# 555_project_analog_swu_board_revA.net
KiCad netlist of a schematic drawn in EAGLE
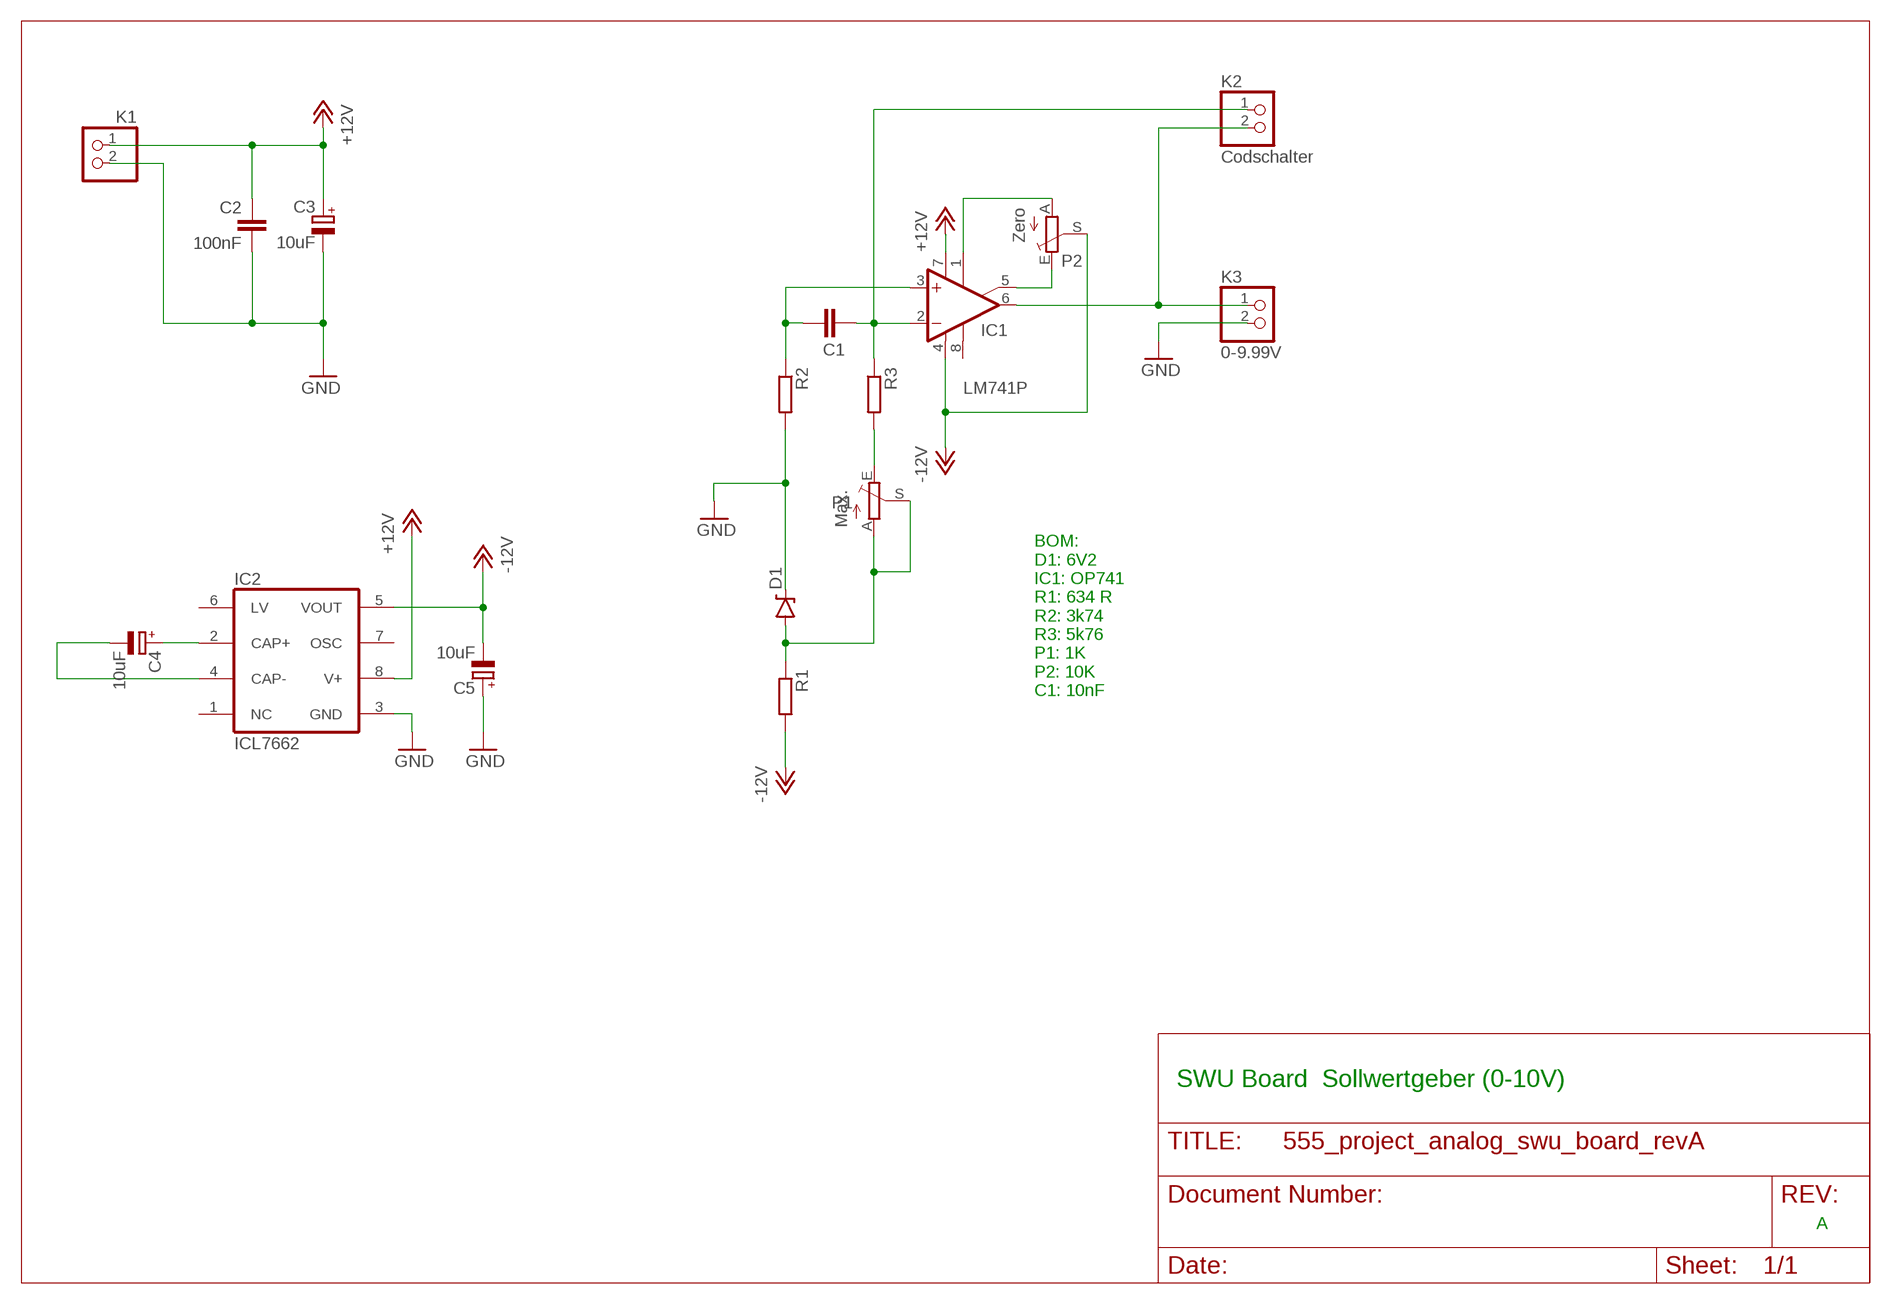
[diagram p0: schematic, sheet 1]

(export (version "E")
  (design (tool "Eeschema 10.0.6"))
  (components
    (comp (ref "C1")
      (value "C-EU025-024X044")
      (footprint "eagle-import:C025-024X044")
      (libsource (lib "eagle-import") (part "C-EU025-024X044"))
    )
    (comp (ref "C2")
      (value "100nF")
      (footprint "eagle-import:C025-024X044")
      (libsource (lib "eagle-import") (part "C-EU025-024X044"))
    )
    (comp (ref "C3")
      (value "10uF")
      (footprint "eagle-import:E2,5-5")
      (libsource (lib "eagle-import") (part "CPOL-EUE2.5-5"))
    )
    (comp (ref "C4")
      (value "10uF")
      (footprint "eagle-import:E2,5-5")
      (libsource (lib "eagle-import") (part "CPOL-EUE2.5-5"))
    )
    (comp (ref "C5")
      (value "10uF")
      (footprint "eagle-import:E2,5-5")
      (libsource (lib "eagle-import") (part "CPOL-EUE2.5-5"))
    )
    (comp (ref "D1")
      (value "DIODE-ZENERPTH")
      (footprint "eagle-import:DIODE-ZENER")
      (libsource (lib "eagle-import") (part "DIODE-ZENERPTH"))
    )
    (comp (ref "IC1")
      (value "LM741P")
      (footprint "eagle-import:DIL08")
      (libsource (lib "eagle-import") (part "741PLM"))
    )
    (comp (ref "IC2")
      (value "ICL7662")
      (footprint "eagle-import:DIL08")
      (fields (field (name "MF") "INTERSIL") (field (name "MPN") "ICL7660CPA"))
      (libsource (lib "eagle-import") (part "ICL7660CPA"))
    )
    (comp (ref "K1")
      (value "PINHD-1X2")
      (footprint "eagle-import:1X02")
      (libsource (lib "eagle-import") (part "PINHD-1X2"))
    )
    (comp (ref "K2")
      (value "Codschalter")
      (footprint "eagle-import:1X02")
      (libsource (lib "eagle-import") (part "PINHD-1X2"))
    )
    (comp (ref "K3")
      (value "0-9.99V")
      (footprint "eagle-import:1X02")
      (libsource (lib "eagle-import") (part "PINHD-1X2"))
    )
    (comp (ref "P1")
      (value "Max.")
      (footprint "eagle-import:LI10")
      (libsource (lib "eagle-import") (part "TRIM_EU-LI10"))
    )
    (comp (ref "P2")
      (value "Zero")
      (footprint "eagle-import:LI10")
      (libsource (lib "eagle-import") (part "TRIM_EU-LI10"))
    )
    (comp (ref "R1")
      (value "R-EU_0207/10")
      (footprint "eagle-import:0207_10")
      (libsource (lib "eagle-import") (part "R-EU_0207/10"))
    )
    (comp (ref "R2")
      (value "R-EU_0207/10")
      (footprint "eagle-import:0207_10")
      (libsource (lib "eagle-import") (part "R-EU_0207/10"))
    )
    (comp (ref "R3")
      (value "R-EU_0207/10")
      (footprint "eagle-import:0207_10")
      (libsource (lib "eagle-import") (part "R-EU_0207/10"))
    )
  )
  (nets
    (net (code "1") (name "+12V") (class "Default")
      (node (ref "C2") (pin "1") (pinfunction "1_1") (pintype "passive"))
      (node (ref "C3") (pin "+") (pinfunction "+_+") (pintype "passive"))
      (node (ref "IC1") (pin "7") (pinfunction "V+_7") (pintype "power_in"))
      (node (ref "IC2") (pin "8") (pinfunction "V+_8") (pintype "power_in"))
      (node (ref "K1") (pin "1") (pinfunction "1_1") (pintype "passive"))
    )
    (net (code "2") (name "-12V") (class "Default")
      (node (ref "C5") (pin "-") (pinfunction "-_-") (pintype "passive"))
      (node (ref "IC1") (pin "4") (pinfunction "V-_4") (pintype "power_in"))
      (node (ref "IC2") (pin "5") (pinfunction "VOUT_5") (pintype "output"))
      (node (ref "P2") (pin "S") (pinfunction "S_S") (pintype "passive"))
      (node (ref "R1") (pin "2") (pinfunction "2_2") (pintype "passive"))
    )
    (net (code "3") (name "GND") (class "Default")
      (node (ref "C2") (pin "2") (pinfunction "2_2") (pintype "passive"))
      (node (ref "C3") (pin "-") (pinfunction "-_-") (pintype "passive"))
      (node (ref "C5") (pin "+") (pinfunction "+_+") (pintype "passive"))
      (node (ref "D1") (pin "P$1") (pinfunction "C_P$1") (pintype "passive"))
      (node (ref "IC2") (pin "3") (pinfunction "GND_3") (pintype "power_in"))
      (node (ref "K1") (pin "2") (pinfunction "2_2") (pintype "passive"))
      (node (ref "K3") (pin "2") (pinfunction "2_2") (pintype "passive"))
      (node (ref "R2") (pin "2") (pinfunction "2_2") (pintype "passive"))
    )
    (net (code "4") (name "Net-(D1-A)") (class "Default")
      (node (ref "D1") (pin "P$2") (pinfunction "A_P$2") (pintype "passive"))
      (node (ref "P1") (pin "A") (pinfunction "A_A") (pintype "passive"))
      (node (ref "P1") (pin "S") (pinfunction "S_S") (pintype "passive"))
      (node (ref "R1") (pin "1") (pinfunction "1_1") (pintype "passive"))
    )
    (net (code "5") (name "Net-(IC1-+IN)") (class "Default")
      (node (ref "C1") (pin "1") (pinfunction "1_1") (pintype "passive"))
      (node (ref "IC1") (pin "3") (pinfunction "+IN_3") (pintype "input"))
      (node (ref "R2") (pin "1") (pinfunction "1_1") (pintype "passive"))
    )
    (net (code "6") (name "Net-(IC1--IN)") (class "Default")
      (node (ref "C1") (pin "2") (pinfunction "2_2") (pintype "passive"))
      (node (ref "IC1") (pin "2") (pinfunction "-IN_2") (pintype "input"))
      (node (ref "K2") (pin "1") (pinfunction "1_1") (pintype "passive"))
      (node (ref "R3") (pin "1") (pinfunction "1_1") (pintype "passive"))
    )
    (net (code "7") (name "Net-(IC1-ON1)") (class "Default")
      (node (ref "IC1") (pin "1") (pinfunction "ON1_1") (pintype "passive"))
      (node (ref "P2") (pin "A") (pinfunction "A_A") (pintype "passive"))
    )
    (net (code "8") (name "Net-(IC1-ON2)") (class "Default")
      (node (ref "IC1") (pin "5") (pinfunction "ON2_5") (pintype "passive"))
      (node (ref "P2") (pin "E") (pinfunction "E_E") (pintype "passive"))
    )
    (net (code "9") (name "Net-(IC1-OUT)") (class "Default")
      (node (ref "IC1") (pin "6") (pinfunction "OUT_6") (pintype "output"))
      (node (ref "K2") (pin "2") (pinfunction "2_2") (pintype "passive"))
      (node (ref "K3") (pin "1") (pinfunction "1_1") (pintype "passive"))
    )
    (net (code "10") (name "Net-(IC2-CAP+)") (class "Default")
      (node (ref "C4") (pin "+") (pinfunction "+_+") (pintype "passive"))
      (node (ref "IC2") (pin "2") (pinfunction "CAP+_2") (pintype "passive"))
    )
    (net (code "11") (name "Net-(IC2-CAP-)") (class "Default")
      (node (ref "C4") (pin "-") (pinfunction "-_-") (pintype "passive"))
      (node (ref "IC2") (pin "4") (pinfunction "CAP-_4") (pintype "passive"))
    )
    (net (code "12") (name "Net-(P1-PadE)") (class "Default")
      (node (ref "P1") (pin "E") (pinfunction "E_E") (pintype "passive"))
      (node (ref "R3") (pin "2") (pinfunction "2_2") (pintype "passive"))
    )
    (net (code "13") (name "unconnected-(IC1-OPT-Pad8)") (class "Default")
      (node (ref "IC1") (pin "8") (pinfunction "OPT_8") (pintype "passive"))
    )
    (net (code "14") (name "unconnected-(IC2-LV-Pad6)") (class "Default")
      (node (ref "IC2") (pin "6") (pinfunction "LV_6") (pintype "passive"))
    )
    (net (code "15") (name "unconnected-(IC2-NC-Pad1)") (class "Default")
      (node (ref "IC2") (pin "1") (pinfunction "NC_1") (pintype "no_connect"))
    )
    (net (code "16") (name "unconnected-(IC2-OSC-Pad7)") (class "Default")
      (node (ref "IC2") (pin "7") (pinfunction "OSC_7") (pintype "output"))
    )
  )
)
